# boost_nguyenLy.net
KiCad netlist of a schematic drawn in Altium Designer
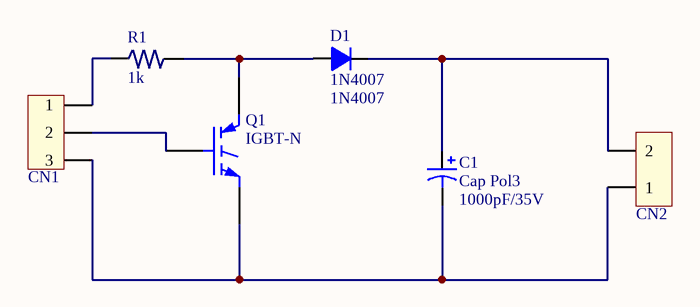
[diagram p0: boost_nguyenLy.SchDoc]

(export (version "E")
  (design (tool "Eeschema 10.0.6"))
  (components
    (comp (ref "C1")
      (value "Cap Pol3")
      (footprint "CP2/5")
      (description "Polarized Capacitor (Surface Mount)")
      (fields (field (name "ALTIUM_VALUE") "1000pF/35V") (field (name "PUBLISHER") "Altium Limited"))
      (libsource (lib "syhaunguyen") (part "Cap Pol3_2"))
    )
    (comp (ref "CN1")
      (value "Con3/Header3")
      (footprint "CON3-2")
      (description "CON3")
      (libsource (lib "sch") (part "Con3/Header3"))
    )
    (comp (ref "CN2")
      (value "Con2/Header2")
      (footprint "CON2-1")
      (description "CON2")
      (libsource (lib "sch") (part "Con2/Header2"))
    )
    (comp (ref "D1")
      (value "1N4007")
      (footprint "Diode")
      (description "Diode")
      (fields (field (name "ALTIUM_VALUE") "1N4007"))
      (libsource (lib "sch") (part "Diode"))
    )
    (comp (ref "Q1")
      (value "IGBT-N")
      (footprint "TO-247")
      (description "Insulated Gate Bipolar Transistor (N-Channel)")
      (fields (field (name "PUBLISHER") "Altium Limited"))
      (libsource (lib "Miscellaneous Devices") (part "IGBT-N"))
    )
    (comp (ref "R1")
      (value "1k")
      (footprint "RESISTOR 2W")
      (description "RESISTOR")
      (libsource (lib "sch") (part "RESISTOR"))
    )
  )
  (nets
    (net (code "1") (name "Net-(CN1-Pad1)") (class "Default")
      (node (ref "CN1") (pin "1") (pinfunction "1_1") (pintype "passive"))
      (node (ref "R1") (pin "1") (pinfunction "1_1") (pintype "passive"))
    )
    (net (code "2") (name "Net-(D1-A)") (class "Default")
      (node (ref "D1") (pin "1") (pinfunction "A_1") (pintype "passive"))
      (node (ref "Q1") (pin "2") (pinfunction "C_2") (pintype "passive"))
      (node (ref "R1") (pin "2") (pinfunction "2_2") (pintype "passive"))
    )
    (net (code "3") (name "Net-(D1-K)") (class "Default")
      (node (ref "C1") (pin "1") (pinfunction "1_1") (pintype "passive"))
      (node (ref "CN2") (pin "2") (pinfunction "2_2") (pintype "passive"))
      (node (ref "D1") (pin "2") (pinfunction "K_2") (pintype "passive"))
    )
    (net (code "4") (name "Net-(Q1-E)") (class "Default")
      (node (ref "C1") (pin "2") (pinfunction "2_2") (pintype "passive"))
      (node (ref "CN1") (pin "3") (pinfunction "3_3") (pintype "passive"))
      (node (ref "CN2") (pin "1") (pinfunction "1_1") (pintype "passive"))
      (node (ref "Q1") (pin "3") (pinfunction "E_3") (pintype "passive"))
    )
    (net (code "5") (name "Net-(Q1-G)") (class "Default")
      (node (ref "CN1") (pin "2") (pinfunction "2_2") (pintype "passive"))
      (node (ref "Q1") (pin "1") (pinfunction "G_1") (pintype "passive"))
    )
  )
)
